# main_Sheet1.net
KiCad netlist of a schematic drawn in Altium Designer
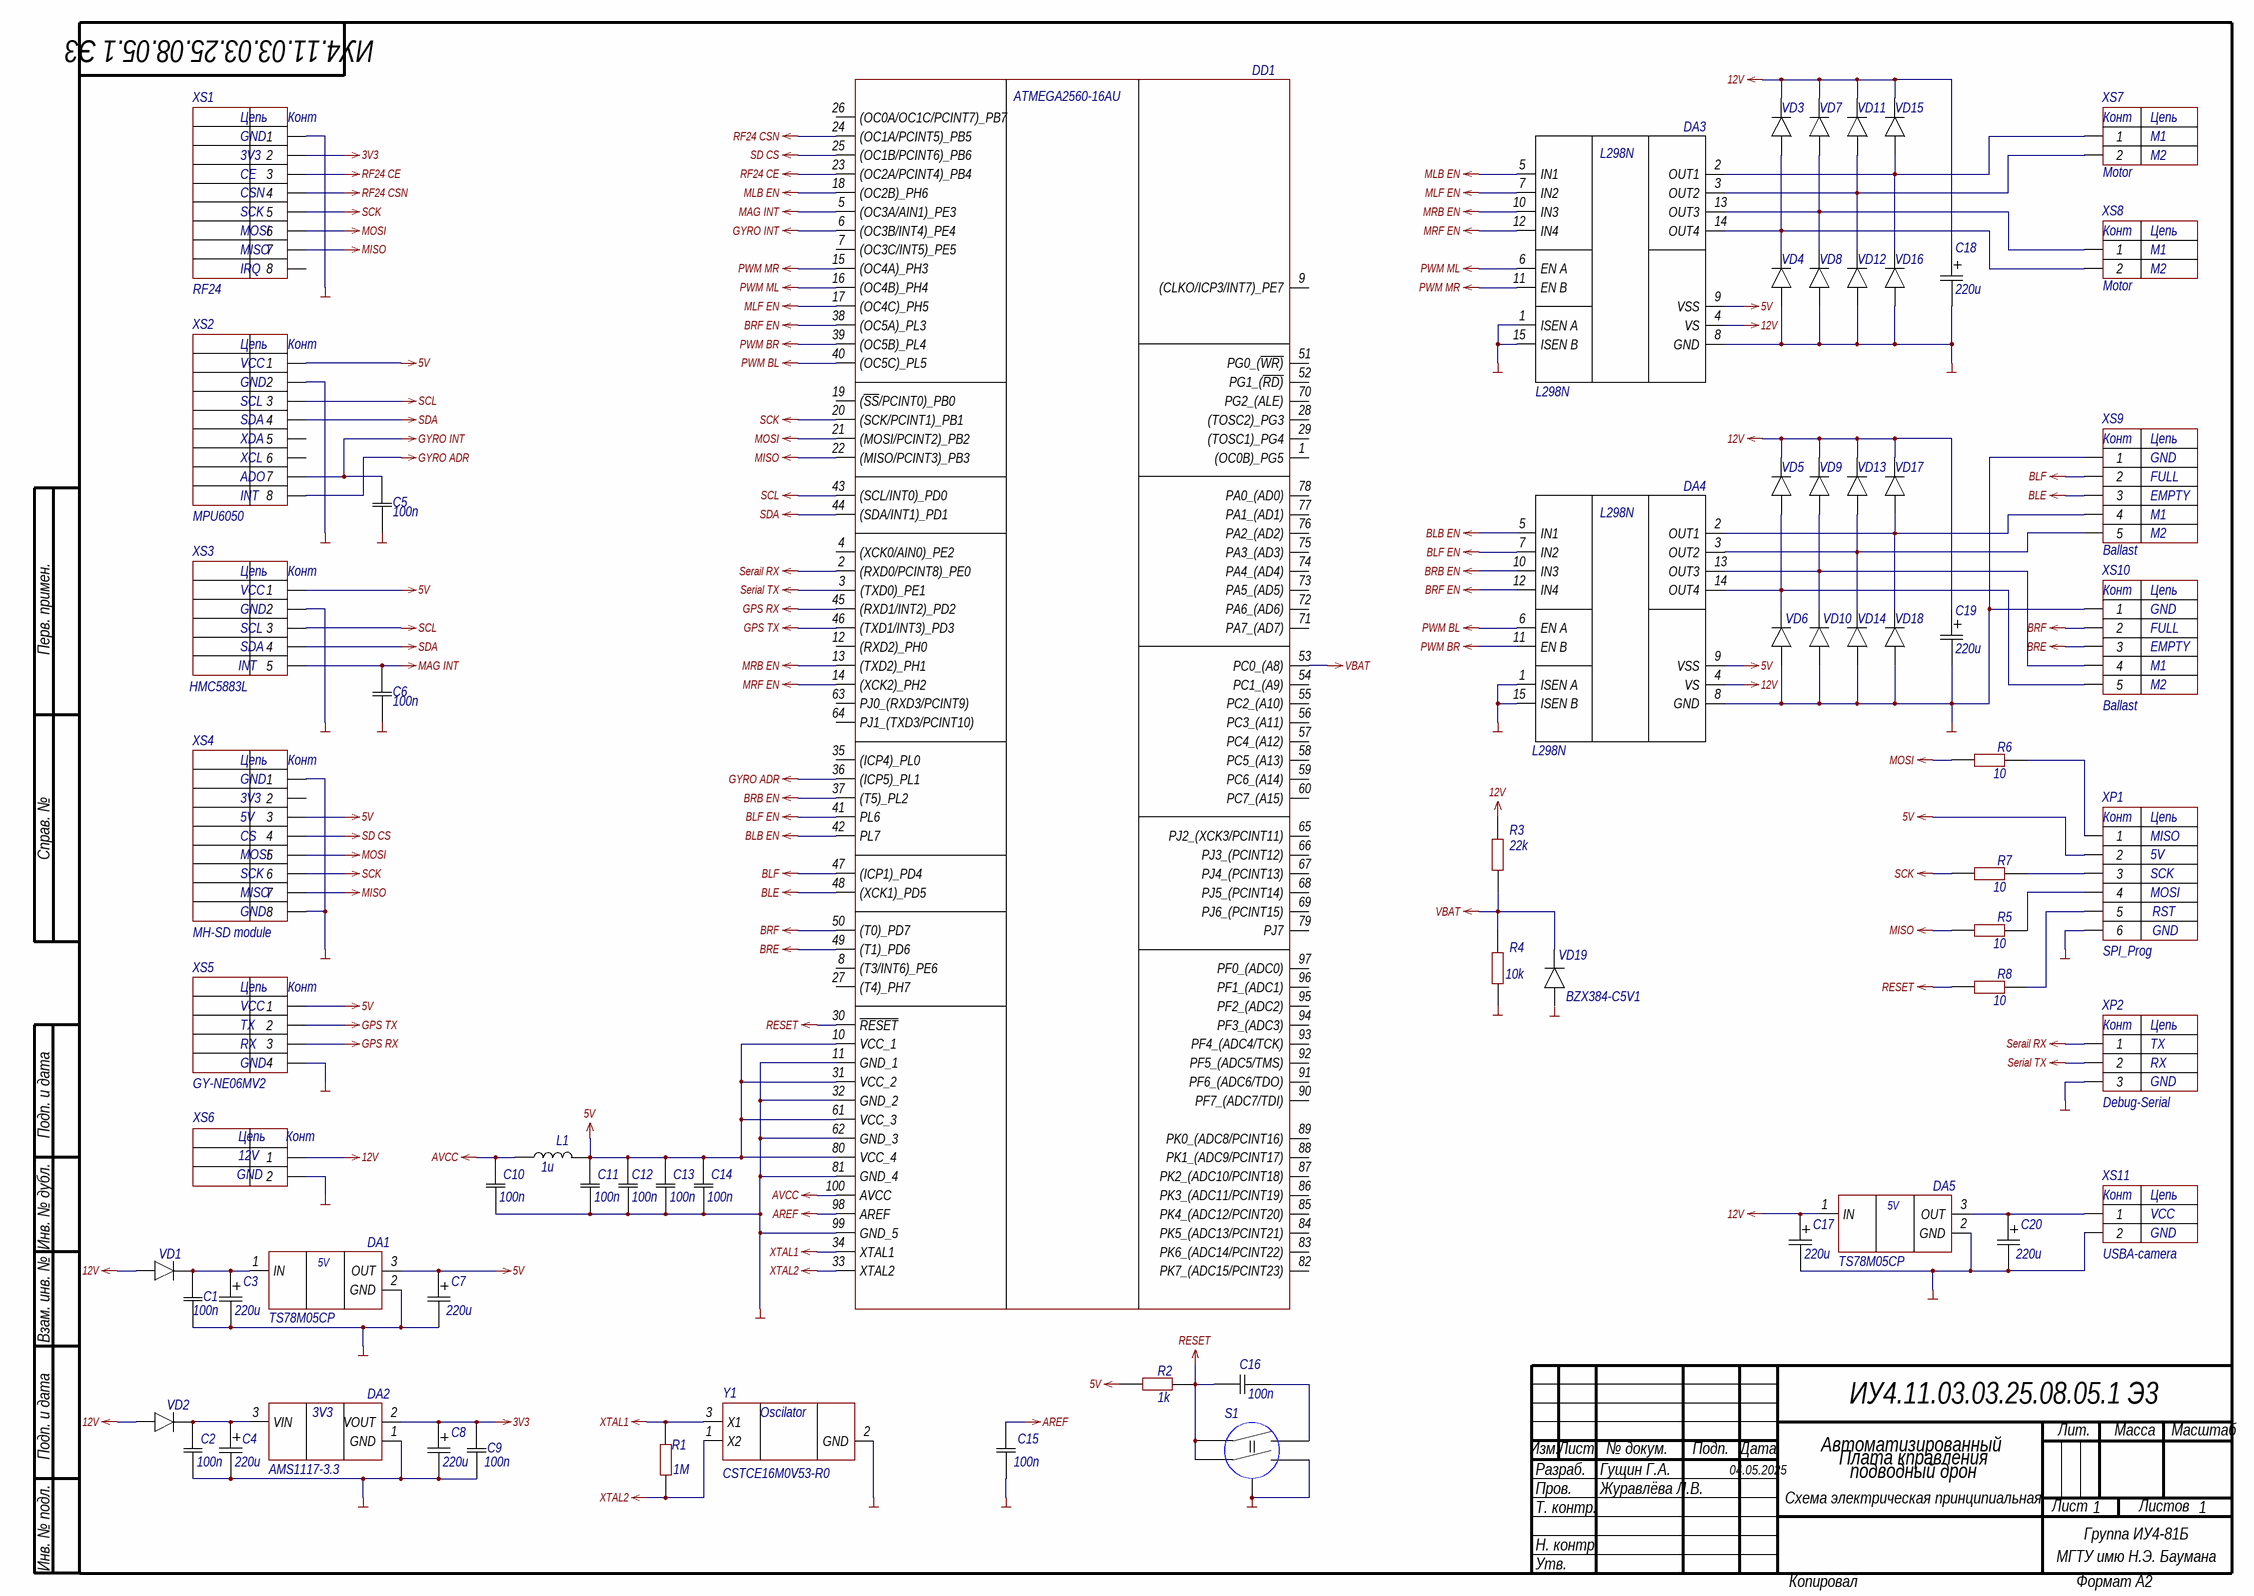
[diagram p0: main_Sheet1.SchDoc]

(export (version "E")
  (design (tool "Eeschema 10.0.6"))
  (components
    (comp (ref "C1")
      (value "100n")
      (footprint "main_PcbLib:CAPC3216X95N")
      (description "Capacitor")
      (fields
        (field (name "MANUFACTURER_PART_NUMBER") "GRM319R72A104KA01D")
        (field (name "MOUSER PART NUMBER") "81-GRM319R72A104KA1D")
      )
      (libsource (lib "main_SchLib") (part "GRM319R72A104KA01D"))
    )
    (comp (ref "C2")
      (value "100n")
      (footprint "main_PcbLib:CAPC3216X95N")
      (description "Capacitor")
      (fields
        (field (name "MANUFACTURER_PART_NUMBER") "GRM319R72A104KA01D")
        (field (name "MOUSER PART NUMBER") "81-GRM319R72A104KA1D")
      )
      (libsource (lib "main_SchLib") (part "GRM319R72A104KA01D"))
    )
    (comp (ref "C3")
      (value "220u")
      (footprint "main_PcbLib:CAPAE830X1050N")
      (description "Capacitor")
      (fields
        (field (name "MANUFACTURER_PART_NUMBER") "EMVY350ADA221MHA0G")
        (field (name "MOUSER PART NUMBER") "661-EMVY350ADA221MHA")
      )
      (libsource (lib "main_SchLib") (part "EMVY350ADA221MHA0G"))
    )
    (comp (ref "C4")
      (value "220u")
      (footprint "main_PcbLib:CAPAE830X1050N")
      (description "Capacitor")
      (fields
        (field (name "MANUFACTURER_PART_NUMBER") "EMVY350ADA221MHA0G")
        (field (name "MOUSER PART NUMBER") "661-EMVY350ADA221MHA")
      )
      (libsource (lib "main_SchLib") (part "EMVY350ADA221MHA0G"))
    )
    (comp (ref "C5")
      (value "100n")
      (footprint "main_PcbLib:CAPC3216X95N")
      (description "Capacitor")
      (fields
        (field (name "MANUFACTURER_PART_NUMBER") "GRM319R72A104KA01D")
        (field (name "MOUSER PART NUMBER") "81-GRM319R72A104KA1D")
      )
      (libsource (lib "main_SchLib") (part "GRM319R72A104KA01D"))
    )
    (comp (ref "C6")
      (value "100n")
      (footprint "main_PcbLib:CAPC3216X95N")
      (description "Capacitor")
      (fields
        (field (name "MANUFACTURER_PART_NUMBER") "GRM319R72A104KA01D")
        (field (name "MOUSER PART NUMBER") "81-GRM319R72A104KA1D")
      )
      (libsource (lib "main_SchLib") (part "GRM319R72A104KA01D"))
    )
    (comp (ref "C7")
      (value "220u")
      (footprint "main_PcbLib:CAPAE830X1050N")
      (description "Capacitor")
      (fields
        (field (name "MANUFACTURER_PART_NUMBER") "EMVY350ADA221MHA0G")
        (field (name "MOUSER PART NUMBER") "661-EMVY350ADA221MHA")
      )
      (libsource (lib "main_SchLib") (part "EMVY350ADA221MHA0G"))
    )
    (comp (ref "C8")
      (value "220u")
      (footprint "main_PcbLib:CAPAE830X1050N")
      (description "Capacitor")
      (fields
        (field (name "MANUFACTURER_PART_NUMBER") "EMVY350ADA221MHA0G")
        (field (name "MOUSER PART NUMBER") "661-EMVY350ADA221MHA")
      )
      (libsource (lib "main_SchLib") (part "EMVY350ADA221MHA0G"))
    )
    (comp (ref "C9")
      (value "100n")
      (footprint "main_PcbLib:CAPC3216X95N")
      (description "Capacitor")
      (fields
        (field (name "MANUFACTURER_PART_NUMBER") "GRM319R72A104KA01D")
        (field (name "MOUSER PART NUMBER") "81-GRM319R72A104KA1D")
      )
      (libsource (lib "main_SchLib") (part "GRM319R72A104KA01D"))
    )
    (comp (ref "C10")
      (value "100n")
      (footprint "main_PcbLib:CAPC3216X95N")
      (description "Capacitor")
      (fields
        (field (name "MANUFACTURER_PART_NUMBER") "GRM319R72A104KA01D")
        (field (name "MOUSER PART NUMBER") "81-GRM319R72A104KA1D")
      )
      (libsource (lib "main_SchLib") (part "GRM319R72A104KA01D"))
    )
    (comp (ref "C11")
      (value "100n")
      (footprint "main_PcbLib:CAPC3216X95N")
      (description "Capacitor")
      (fields
        (field (name "MANUFACTURER_PART_NUMBER") "GRM319R72A104KA01D")
        (field (name "MOUSER PART NUMBER") "81-GRM319R72A104KA1D")
      )
      (libsource (lib "main_SchLib") (part "GRM319R72A104KA01D"))
    )
    (comp (ref "C12")
      (value "100n")
      (footprint "main_PcbLib:CAPC3216X95N")
      (description "Capacitor")
      (fields
        (field (name "MANUFACTURER_PART_NUMBER") "GRM319R72A104KA01D")
        (field (name "MOUSER PART NUMBER") "81-GRM319R72A104KA1D")
      )
      (libsource (lib "main_SchLib") (part "GRM319R72A104KA01D"))
    )
    (comp (ref "C13")
      (value "100n")
      (footprint "main_PcbLib:CAPC3216X95N")
      (description "Capacitor")
      (fields
        (field (name "MANUFACTURER_PART_NUMBER") "GRM319R72A104KA01D")
        (field (name "MOUSER PART NUMBER") "81-GRM319R72A104KA1D")
      )
      (libsource (lib "main_SchLib") (part "GRM319R72A104KA01D"))
    )
    (comp (ref "C14")
      (value "100n")
      (footprint "main_PcbLib:CAPC3216X95N")
      (description "Capacitor")
      (fields
        (field (name "MANUFACTURER_PART_NUMBER") "GRM319R72A104KA01D")
        (field (name "MOUSER PART NUMBER") "81-GRM319R72A104KA1D")
      )
      (libsource (lib "main_SchLib") (part "GRM319R72A104KA01D"))
    )
    (comp (ref "C15")
      (value "100n")
      (footprint "main_PcbLib:CAPC3216X95N")
      (description "Capacitor")
      (fields
        (field (name "MANUFACTURER_PART_NUMBER") "GRM319R72A104KA01D")
        (field (name "MOUSER PART NUMBER") "81-GRM319R72A104KA1D")
      )
      (libsource (lib "main_SchLib") (part "GRM319R72A104KA01D"))
    )
    (comp (ref "C16")
      (value "100n")
      (footprint "main_PcbLib:CAPC3216X95N")
      (description "Capacitor")
      (fields
        (field (name "MANUFACTURER_PART_NUMBER") "GRM319R72A104KA01D")
        (field (name "MOUSER PART NUMBER") "81-GRM319R72A104KA1D")
      )
      (libsource (lib "main_SchLib") (part "GRM319R72A104KA01D"))
    )
    (comp (ref "C17")
      (value "220u")
      (footprint "main_PcbLib:CAPAE830X1050N")
      (description "Capacitor")
      (fields
        (field (name "MANUFACTURER_PART_NUMBER") "EMVY350ADA221MHA0G")
        (field (name "MOUSER PART NUMBER") "661-EMVY350ADA221MHA")
      )
      (libsource (lib "main_SchLib") (part "EMVY350ADA221MHA0G"))
    )
    (comp (ref "C18")
      (value "220u")
      (footprint "main_PcbLib:CAPAE830X1050N")
      (description "Capacitor")
      (fields
        (field (name "MANUFACTURER_PART_NUMBER") "EMVY350ADA221MHA0G")
        (field (name "MOUSER PART NUMBER") "661-EMVY350ADA221MHA")
      )
      (libsource (lib "main_SchLib") (part "EMVY350ADA221MHA0G"))
    )
    (comp (ref "C19")
      (value "220u")
      (footprint "main_PcbLib:CAPAE830X1050N")
      (description "Capacitor")
      (fields
        (field (name "MANUFACTURER_PART_NUMBER") "EMVY350ADA221MHA0G")
        (field (name "MOUSER PART NUMBER") "661-EMVY350ADA221MHA")
      )
      (libsource (lib "main_SchLib") (part "EMVY350ADA221MHA0G"))
    )
    (comp (ref "C20")
      (value "220u")
      (footprint "main_PcbLib:CAPAE830X1050N")
      (description "Capacitor")
      (fields
        (field (name "MANUFACTURER_PART_NUMBER") "EMVY350ADA221MHA0G")
        (field (name "MOUSER PART NUMBER") "661-EMVY350ADA221MHA")
      )
      (libsource (lib "main_SchLib") (part "EMVY350ADA221MHA0G"))
    )
    (comp (ref "DA1")
      (value "TS78M05CP")
      (footprint "main_PcbLib:TS78M05CP")
      (description "Integrated Circuit")
      (fields (field (name "MOUSER PART NUMBER") "821-TS78M05CP"))
      (libsource (lib "main_SchLib") (part "TS78M05CP"))
    )
    (comp (ref "DA2")
      (value "AMS1117-3.3")
      (footprint "main_PcbLib:SOT229P700X180-4N")
      (description "Integrated Circuit")
      (libsource (lib "main_SchLib") (part "AMS1117-3.3"))
    )
    (comp (ref "DA3")
      (value "L298N")
      (footprint "main_PcbLib:TO127P500X2020X2210-15P")
      (description "Integrated Circuit")
      (fields (field (name "MOUSER PART NUMBER") "511-L298"))
      (libsource (lib "main_SchLib") (part "L298N"))
    )
    (comp (ref "DA4")
      (value "L298N")
      (footprint "main_PcbLib:TO127P500X2020X2210-15P")
      (description "Integrated Circuit")
      (fields (field (name "MOUSER PART NUMBER") "511-L298"))
      (libsource (lib "main_SchLib") (part "L298N"))
    )
    (comp (ref "DA5")
      (value "TS78M05CP")
      (footprint "main_PcbLib:TS78M05CP")
      (description "Integrated Circuit")
      (fields (field (name "MOUSER PART NUMBER") "821-TS78M05CP"))
      (libsource (lib "main_SchLib") (part "TS78M05CP"))
    )
    (comp (ref "DD1")
      (value "ATMEGA2560-16AU")
      (footprint "main_PcbLib:QFP50P1600X1600X120-100N")
      (description "Integrated Circuit")
      (fields (field (name "MOUSER PART NUMBER") "556-ATMEGA2560-16AU"))
      (libsource (lib "main_SchLib") (part "ATMEGA2560-16AU"))
    )
    (comp (ref "L1")
      (value "1u")
      (footprint "main_PcbLib:INDPM3225X240N")
      (description "Inductor")
      (fields
        (field (name "MANUFACTURER_PART_NUMBER") "NLCV32T-1R0M-EF")
        (field (name "MOUSER PART NUMBER") "810-NLCV32T-1R0M-EF")
      )
      (libsource (lib "main_SchLib") (part "NLCV32T-1R0M-EF"))
    )
    (comp (ref "R1")
      (value "1M")
      (footprint "main_PcbLib:RESC3126X65N")
      (description "Resistor")
      (fields (field (name "MANUFACTURER_PART_NUMBER") "MP000277"))
      (libsource (lib "main_SchLib") (part "1M"))
    )
    (comp (ref "R2")
      (value "1k")
      (footprint "main_PcbLib:RESC3126X65N")
      (description "Resistor")
      (fields (field (name "MANUFACTURER_PART_NUMBER") "MP000277"))
      (libsource (lib "main_SchLib") (part "1k"))
    )
    (comp (ref "R3")
      (value "22k")
      (footprint "main_PcbLib:RESC3126X65N")
      (description "Resistor")
      (fields (field (name "MANUFACTURER_PART_NUMBER") "MP000277"))
      (libsource (lib "main_SchLib") (part "10k"))
    )
    (comp (ref "R4")
      (value "10k")
      (footprint "main_PcbLib:RESC3126X65N")
      (description "Resistor")
      (fields (field (name "MANUFACTURER_PART_NUMBER") "MP000277"))
      (libsource (lib "main_SchLib") (part "22k"))
    )
    (comp (ref "R5")
      (value "10")
      (footprint "main_PcbLib:RESC3126X65N")
      (description "Resistor")
      (fields (field (name "MANUFACTURER_PART_NUMBER") "MP000277"))
      (libsource (lib "main_SchLib") (part "10"))
    )
    (comp (ref "R6")
      (value "10")
      (footprint "main_PcbLib:RESC3126X65N")
      (description "Resistor")
      (fields (field (name "MANUFACTURER_PART_NUMBER") "MP000277"))
      (libsource (lib "main_SchLib") (part "10"))
    )
    (comp (ref "R7")
      (value "10")
      (footprint "main_PcbLib:RESC3126X65N")
      (description "Resistor")
      (fields (field (name "MANUFACTURER_PART_NUMBER") "MP000277"))
      (libsource (lib "main_SchLib") (part "10"))
    )
    (comp (ref "R8")
      (value "10")
      (footprint "main_PcbLib:RESC3126X65N")
      (description "Resistor")
      (fields (field (name "MANUFACTURER_PART_NUMBER") "MP000277"))
      (libsource (lib "main_SchLib") (part "10"))
    )
    (comp (ref "S1")
      (value "FSM1LPASTR")
      (footprint "main_PcbLib:FSM1LPASTR")
      (description "Switch")
      (fields (field (name "MOUSER PART NUMBER") "506-FSM1LPASTR"))
      (libsource (lib "main_SchLib") (part "FSM1LPASTR"))
    )
    (comp (ref "VD1")
      (value "~")
      (footprint "main_PcbLib:1N4007W")
      (description "Diode")
      (fields (field (name "MANUFACTURER_PART_NUMBER") "1N4007W"))
      (libsource (lib "main_SchLib") (part "1N4007W"))
    )
    (comp (ref "VD2")
      (value "1N4007W")
      (footprint "main_PcbLib:1N4007W")
      (description "Diode")
      (libsource (lib "main_SchLib") (part "1N4007W"))
    )
    (comp (ref "VD3")
      (value "1N4007W")
      (footprint "main_PcbLib:1N4007W")
      (description "Diode")
      (libsource (lib "main_SchLib") (part "1N4007W"))
    )
    (comp (ref "VD4")
      (value "1N4007W")
      (footprint "main_PcbLib:1N4007W")
      (description "Diode")
      (libsource (lib "main_SchLib") (part "1N4007W"))
    )
    (comp (ref "VD5")
      (value "1N4007W")
      (footprint "main_PcbLib:1N4007W")
      (description "Diode")
      (libsource (lib "main_SchLib") (part "1N4007W"))
    )
    (comp (ref "VD6")
      (value "1N4007W")
      (footprint "main_PcbLib:1N4007W")
      (description "Diode")
      (libsource (lib "main_SchLib") (part "1N4007W"))
    )
    (comp (ref "VD7")
      (value "1N4007W")
      (footprint "main_PcbLib:1N4007W")
      (description "Diode")
      (libsource (lib "main_SchLib") (part "1N4007W"))
    )
    (comp (ref "VD8")
      (value "1N4007W")
      (footprint "main_PcbLib:1N4007W")
      (description "Diode")
      (libsource (lib "main_SchLib") (part "1N4007W"))
    )
    (comp (ref "VD9")
      (value "1N4007W")
      (footprint "main_PcbLib:1N4007W")
      (description "Diode")
      (libsource (lib "main_SchLib") (part "1N4007W"))
    )
    (comp (ref "VD10")
      (value "1N4007W")
      (footprint "main_PcbLib:1N4007W")
      (description "Diode")
      (libsource (lib "main_SchLib") (part "1N4007W"))
    )
    (comp (ref "VD11")
      (value "1N4007W")
      (footprint "main_PcbLib:1N4007W")
      (description "Diode")
      (libsource (lib "main_SchLib") (part "1N4007W"))
    )
    (comp (ref "VD12")
      (value "1N4007W")
      (footprint "main_PcbLib:1N4007W")
      (description "Diode")
      (libsource (lib "main_SchLib") (part "1N4007W"))
    )
    (comp (ref "VD13")
      (value "1N4007W")
      (footprint "main_PcbLib:1N4007W")
      (description "Diode")
      (libsource (lib "main_SchLib") (part "1N4007W"))
    )
    (comp (ref "VD14")
      (value "1N4007W")
      (footprint "main_PcbLib:1N4007W")
      (description "Diode")
      (libsource (lib "main_SchLib") (part "1N4007W"))
    )
    (comp (ref "VD15")
      (value "1N4007W")
      (footprint "main_PcbLib:1N4007W")
      (description "Diode")
      (libsource (lib "main_SchLib") (part "1N4007W"))
    )
    (comp (ref "VD16")
      (value "1N4007W")
      (footprint "main_PcbLib:1N4007W")
      (description "Diode")
      (libsource (lib "main_SchLib") (part "1N4007W"))
    )
    (comp (ref "VD17")
      (value "1N4007W")
      (footprint "main_PcbLib:1N4007W")
      (description "Diode")
      (libsource (lib "main_SchLib") (part "1N4007W"))
    )
    (comp (ref "VD18")
      (value "1N4007W")
      (footprint "main_PcbLib:1N4007W")
      (description "Diode")
      (libsource (lib "main_SchLib") (part "1N4007W"))
    )
    (comp (ref "VD19")
      (value "BZX384-C5V1")
      (footprint "main_PcbLib:SOD2512X110N")
      (description "Diode")
      (libsource (lib "main_SchLib") (part "BZX384-C5V1"))
    )
    (comp (ref "XP1")
      (value "SPI_Prog")
      (footprint "PLS_2x3")
      (description "Connector")
      (libsource (lib "main_SchLib") (part "SPI_Prog"))
    )
    (comp (ref "XP2")
      (value "Debug-Serial")
      (footprint "PLS_1x3")
      (description "Connector")
      (libsource (lib "main_SchLib") (part "Debug-Serial"))
    )
    (comp (ref "XS1")
      (value "RF24")
      (footprint "nRF24")
      (description "Connector")
      (libsource (lib "main_SchLib") (part "nRF24"))
    )
    (comp (ref "XS2")
      (value "MPU6050")
      (footprint "MPU6050")
      (description "Connector")
      (libsource (lib "main_SchLib") (part "MPU6050"))
    )
    (comp (ref "XS3")
      (value "HMC5883L")
      (footprint "HMC5883L")
      (description "Connector")
      (libsource (lib "main_SchLib") (part "HMC5883L"))
    )
    (comp (ref "XS4")
      (value "MH-SD module")
      (footprint "SD-module")
      (description "Connector")
      (libsource (lib "main_SchLib") (part "MH-SD module"))
    )
    (comp (ref "XS5")
      (value "GY-NE06MV2")
      (footprint "GY-GPS")
      (description "Connector")
      (libsource (lib "main_SchLib") (part "GY-NE06MV2"))
    )
    (comp (ref "XS6")
      (value "XT60PW-M")
      (footprint "main_PcbLib:XT60PWM")
      (description "Connector")
      (libsource (lib "main_SchLib") (part "XT60PW-M"))
    )
    (comp (ref "XS7")
      (value "Motor")
      (footprint "S2B-XH-A-1")
      (description "Connector")
      (libsource (lib "main_SchLib") (part "Motor"))
    )
    (comp (ref "XS8")
      (value "Motor")
      (footprint "S2B-XH-A-1")
      (description "Connector")
      (libsource (lib "main_SchLib") (part "Motor"))
    )
    (comp (ref "XS9")
      (value "Ballast")
      (footprint "S5B-XH-A-1")
      (description "Connector")
      (libsource (lib "main_SchLib") (part "Ballast"))
    )
    (comp (ref "XS10")
      (value "Ballast")
      (footprint "S5B-XH-A-1")
      (description "Connector")
      (libsource (lib "main_SchLib") (part "Ballast"))
    )
    (comp (ref "XS11")
      (value "USBA-camera")
      (footprint "TYPE-C-SMD")
      (description "Connector")
      (libsource (lib "main_SchLib") (part "USBA-camera"))
    )
    (comp (ref "Y1")
      (value "CSTCE16M0V53-R0")
      (footprint "main_PcbLib:CSTCE16M0V53R0")
      (description "Oscillator")
      (fields (field (name "MOUSER PART NUMBER") "81-CSTCE16M0V53-R0"))
      (libsource (lib "main_SchLib") (part "CSTCE16M0V53-R0"))
    )
  )
  (nets
    (net (code "1") (name "3V3") (class "Default")
      (node (ref "C8") (pin "1") (pinfunction "+_1") (pintype "passive"))
      (node (ref "C9") (pin "1") (pinfunction "1_1") (pintype "passive"))
      (node (ref "DA2") (pin "2") (pinfunction "VOUT_2") (pintype "passive"))
      (node (ref "XS1") (pin "2") (pinfunction "2_2") (pintype "passive"))
    )
    (net (code "2") (name "5V") (class "Default")
      (node (ref "C11") (pin "1") (pinfunction "1_1") (pintype "passive"))
      (node (ref "C12") (pin "1") (pinfunction "1_1") (pintype "passive"))
      (node (ref "C13") (pin "1") (pinfunction "1_1") (pintype "passive"))
      (node (ref "C14") (pin "1") (pinfunction "1_1") (pintype "passive"))
      (node (ref "C7") (pin "1") (pinfunction "+_1") (pintype "passive"))
      (node (ref "DA1") (pin "3") (pinfunction "OUT_3") (pintype "passive"))
      (node (ref "DA3") (pin "9") (pinfunction "VSS_9") (pintype "power_in"))
      (node (ref "DA4") (pin "9") (pinfunction "VSS_9") (pintype "power_in"))
      (node (ref "DD1") (pin "10") (pinfunction "VCC_1_10") (pintype "passive"))
      (node (ref "DD1") (pin "31") (pinfunction "VCC_2_31") (pintype "passive"))
      (node (ref "DD1") (pin "61") (pinfunction "VCC_3_61") (pintype "passive"))
      (node (ref "DD1") (pin "80") (pinfunction "VCC_4_80") (pintype "passive"))
      (node (ref "L1") (pin "2") (pinfunction "2_2") (pintype "passive"))
      (node (ref "R2") (pin "1") (pinfunction "1_1") (pintype "passive"))
      (node (ref "XP1") (pin "2") (pinfunction "2_2") (pintype "passive"))
      (node (ref "XS2") (pin "1") (pinfunction "1_1") (pintype "passive"))
      (node (ref "XS3") (pin "1") (pinfunction "1_1") (pintype "passive"))
      (node (ref "XS4") (pin "3") (pinfunction "3_3") (pintype "passive"))
      (node (ref "XS5") (pin "1") (pinfunction "1_1") (pintype "passive"))
    )
    (net (code "3") (name "12V") (class "Default")
      (node (ref "C17") (pin "1") (pinfunction "+_1") (pintype "passive"))
      (node (ref "C18") (pin "1") (pinfunction "+_1") (pintype "passive"))
      (node (ref "C19") (pin "1") (pinfunction "+_1") (pintype "passive"))
      (node (ref "DA3") (pin "4") (pinfunction "VS_4") (pintype "power_in"))
      (node (ref "DA4") (pin "4") (pinfunction "VS_4") (pintype "power_in"))
      (node (ref "DA5") (pin "1") (pinfunction "IN_1") (pintype "passive"))
      (node (ref "R3") (pin "2") (pinfunction "2_2") (pintype "passive"))
      (node (ref "VD1") (pin "2") (pinfunction "A_2") (pintype "passive"))
      (node (ref "VD11") (pin "1") (pinfunction "K_1") (pintype "passive"))
      (node (ref "VD13") (pin "1") (pinfunction "K_1") (pintype "passive"))
      (node (ref "VD15") (pin "1") (pinfunction "K_1") (pintype "passive"))
      (node (ref "VD17") (pin "1") (pinfunction "K_1") (pintype "passive"))
      (node (ref "VD2") (pin "2") (pinfunction "A_2") (pintype "passive"))
      (node (ref "VD3") (pin "1") (pinfunction "K_1") (pintype "passive"))
      (node (ref "VD5") (pin "1") (pinfunction "K_1") (pintype "passive"))
      (node (ref "VD7") (pin "1") (pinfunction "K_1") (pintype "passive"))
      (node (ref "VD9") (pin "1") (pinfunction "K_1") (pintype "passive"))
      (node (ref "XS6") (pin "1") (pinfunction "1_1") (pintype "passive"))
    )
    (net (code "4") (name "AREF") (class "Default")
      (node (ref "C15") (pin "1") (pinfunction "1_1") (pintype "passive"))
      (node (ref "DD1") (pin "98") (pinfunction "AREF_98") (pintype "passive"))
    )
    (net (code "5") (name "AVCC") (class "Default")
      (node (ref "C10") (pin "1") (pinfunction "1_1") (pintype "passive"))
      (node (ref "DD1") (pin "100") (pinfunction "AVCC_100") (pintype "passive"))
      (node (ref "L1") (pin "1") (pinfunction "1_1") (pintype "passive"))
    )
    (net (code "6") (name "BLB EN") (class "Default")
      (node (ref "DA4") (pin "5") (pinfunction "IN1_5") (pintype "power_in"))
      (node (ref "DD1") (pin "42") (pinfunction "PL7_42") (pintype "passive"))
    )
    (net (code "7") (name "BLE") (class "Default")
      (node (ref "DD1") (pin "48") (pinfunction "(XCK1)_PD5_48") (pintype "passive"))
      (node (ref "XS9") (pin "3") (pinfunction "3_3") (pintype "passive"))
    )
    (net (code "8") (name "BLF") (class "Default")
      (node (ref "DD1") (pin "47") (pinfunction "(ICP1)_PD4_47") (pintype "passive"))
      (node (ref "XS9") (pin "2") (pinfunction "2_2") (pintype "passive"))
    )
    (net (code "9") (name "BLF EN") (class "Default")
      (node (ref "DA4") (pin "7") (pinfunction "IN2_7") (pintype "power_in"))
      (node (ref "DD1") (pin "41") (pinfunction "PL6_41") (pintype "passive"))
    )
    (net (code "10") (name "BRB EN") (class "Default")
      (node (ref "DA4") (pin "10") (pinfunction "IN3_10") (pintype "power_in"))
      (node (ref "DD1") (pin "37") (pinfunction "(T5)_PL2_37") (pintype "passive"))
    )
    (net (code "11") (name "BRE") (class "Default")
      (node (ref "DD1") (pin "49") (pinfunction "(T1)_PD6_49") (pintype "passive"))
      (node (ref "XS10") (pin "3") (pinfunction "3_3") (pintype "passive"))
    )
    (net (code "12") (name "BRF") (class "Default")
      (node (ref "DD1") (pin "50") (pinfunction "(T0)_PD7_50") (pintype "passive"))
      (node (ref "XS10") (pin "2") (pinfunction "2_2") (pintype "passive"))
    )
    (net (code "13") (name "BRF EN") (class "Default")
      (node (ref "DA4") (pin "12") (pinfunction "IN4_12") (pintype "power_in"))
      (node (ref "DD1") (pin "38") (pinfunction "(OC5A)_PL3_38") (pintype "passive"))
    )
    (net (code "14") (name "GND") (class "Default")
      (node (ref "C1") (pin "2") (pinfunction "2_2") (pintype "passive"))
      (node (ref "C10") (pin "2") (pinfunction "2_2") (pintype "passive"))
      (node (ref "C11") (pin "2") (pinfunction "2_2") (pintype "passive"))
      (node (ref "C12") (pin "2") (pinfunction "2_2") (pintype "passive"))
      (node (ref "C13") (pin "2") (pinfunction "2_2") (pintype "passive"))
      (node (ref "C14") (pin "2") (pinfunction "2_2") (pintype "passive"))
      (node (ref "C15") (pin "2") (pinfunction "2_2") (pintype "passive"))
      (node (ref "C17") (pin "2") (pinfunction "-_2") (pintype "passive"))
      (node (ref "C18") (pin "2") (pinfunction "-_2") (pintype "passive"))
      (node (ref "C19") (pin "2") (pinfunction "-_2") (pintype "passive"))
      (node (ref "C2") (pin "2") (pinfunction "2_2") (pintype "passive"))
      (node (ref "C20") (pin "2") (pinfunction "-_2") (pintype "passive"))
      (node (ref "C3") (pin "2") (pinfunction "-_2") (pintype "passive"))
      (node (ref "C4") (pin "2") (pinfunction "-_2") (pintype "passive"))
      (node (ref "C5") (pin "2") (pinfunction "2_2") (pintype "passive"))
      (node (ref "C6") (pin "2") (pinfunction "2_2") (pintype "passive"))
      (node (ref "C7") (pin "2") (pinfunction "-_2") (pintype "passive"))
      (node (ref "C8") (pin "2") (pinfunction "-_2") (pintype "passive"))
      (node (ref "C9") (pin "2") (pinfunction "2_2") (pintype "passive"))
      (node (ref "DA1") (pin "2") (pinfunction "GND_2") (pintype "passive"))
      (node (ref "DA2") (pin "1") (pinfunction "GND_1") (pintype "passive"))
      (node (ref "DA3") (pin "1") (pinfunction "ISEN_A_1") (pintype "power_in"))
      (node (ref "DA3") (pin "15") (pinfunction "ISEN_B_15") (pintype "power_in"))
      (node (ref "DA3") (pin "8") (pinfunction "GND_8") (pintype "power_in"))
      (node (ref "DA4") (pin "1") (pinfunction "ISEN_A_1") (pintype "power_in"))
      (node (ref "DA4") (pin "15") (pinfunction "ISEN_B_15") (pintype "power_in"))
      (node (ref "DA4") (pin "8") (pinfunction "GND_8") (pintype "power_in"))
      (node (ref "DA5") (pin "2") (pinfunction "GND_2") (pintype "passive"))
      (node (ref "DD1") (pin "11") (pinfunction "GND_1_11") (pintype "passive"))
      (node (ref "DD1") (pin "32") (pinfunction "GND_2_32") (pintype "passive"))
      (node (ref "DD1") (pin "62") (pinfunction "GND_3_62") (pintype "passive"))
      (node (ref "DD1") (pin "81") (pinfunction "GND_4_81") (pintype "passive"))
      (node (ref "DD1") (pin "99") (pinfunction "GND_5_99") (pintype "passive"))
      (node (ref "R4") (pin "1") (pinfunction "1_1") (pintype "passive"))
      (node (ref "S1") (pin "4") (pinfunction "NO_2_4") (pintype "passive"))
      (node (ref "S1") (pin "5") (pinfunction "GND_5") (pintype "passive"))
      (node (ref "VD10") (pin "2") (pinfunction "A_2") (pintype "passive"))
      (node (ref "VD12") (pin "2") (pinfunction "A_2") (pintype "passive"))
      (node (ref "VD14") (pin "2") (pinfunction "A_2") (pintype "passive"))
      (node (ref "VD16") (pin "2") (pinfunction "A_2") (pintype "passive"))
      (node (ref "VD18") (pin "2") (pinfunction "A_2") (pintype "passive"))
      (node (ref "VD4") (pin "2") (pinfunction "A_2") (pintype "passive"))
      (node (ref "VD6") (pin "2") (pinfunction "A_2") (pintype "passive"))
      (node (ref "VD8") (pin "2") (pinfunction "A_2") (pintype "passive"))
      (node (ref "XP1") (pin "6") (pinfunction "6_6") (pintype "passive"))
      (node (ref "XP2") (pin "3") (pinfunction "3_3") (pintype "passive"))
      (node (ref "XS1") (pin "1") (pinfunction "1_1") (pintype "passive"))
      (node (ref "XS10") (pin "1") (pinfunction "1_1") (pintype "passive"))
      (node (ref "XS11") (pin "4") (pinfunction "2_4") (pintype "passive"))
      (node (ref "XS2") (pin "2") (pinfunction "2_2") (pintype "passive"))
      (node (ref "XS3") (pin "2") (pinfunction "2_2") (pintype "passive"))
      (node (ref "XS4") (pin "1") (pinfunction "1_1") (pintype "passive"))
      (node (ref "XS4") (pin "8") (pinfunction "8_8") (pintype "passive"))
      (node (ref "XS5") (pin "4") (pinfunction "4_4") (pintype "passive"))
      (node (ref "XS6") (pin "2") (pinfunction "2_2") (pintype "passive"))
      (node (ref "XS9") (pin "1") (pinfunction "1_1") (pintype "passive"))
      (node (ref "Y1") (pin "2") (pinfunction "GND_2") (pintype "passive"))
    )
    (net (code "15") (name "GPS RX") (class "Default")
      (node (ref "DD1") (pin "45") (pinfunction "(RXD1/INT2)_PD2_45") (pintype "passive"))
      (node (ref "XS5") (pin "3") (pinfunction "3_3") (pintype "passive"))
    )
    (net (code "16") (name "GPS TX") (class "Default")
      (node (ref "DD1") (pin "46") (pinfunction "(TXD1/INT3)_PD3_46") (pintype "passive"))
      (node (ref "XS5") (pin "2") (pinfunction "2_2") (pintype "passive"))
    )
    (net (code "17") (name "GYRO ADR") (class "Default")
      (node (ref "DD1") (pin "36") (pinfunction "(ICP5)_PL1_36") (pintype "passive"))
      (node (ref "XS2") (pin "8") (pinfunction "8_8") (pintype "passive"))
    )
    (net (code "18") (name "GYRO INT") (class "Default")
      (node (ref "C5") (pin "1") (pinfunction "1_1") (pintype "passive"))
      (node (ref "DD1") (pin "6") (pinfunction "(OC3B/INT4)_PE4_6") (pintype "passive"))
      (node (ref "XS2") (pin "7") (pinfunction "7_7") (pintype "passive"))
    )
    (net (code "19") (name "MAG INT") (class "Default")
      (node (ref "C6") (pin "1") (pinfunction "1_1") (pintype "passive"))
      (node (ref "DD1") (pin "5") (pinfunction "(OC3A/AIN1)_PE3_5") (pintype "passive"))
      (node (ref "XS3") (pin "5") (pinfunction "5_5") (pintype "passive"))
    )
    (net (code "20") (name "MISO") (class "Default")
      (node (ref "DD1") (pin "22") (pinfunction "(MISO/PCINT3)_PB3_22") (pintype "passive"))
      (node (ref "R5") (pin "1") (pinfunction "1_1") (pintype "passive"))
      (node (ref "XS1") (pin "7") (pinfunction "7_7") (pintype "passive"))
      (node (ref "XS4") (pin "7") (pinfunction "7_7") (pintype "passive"))
    )
    (net (code "21") (name "MLB EN") (class "Default")
      (node (ref "DA3") (pin "5") (pinfunction "IN1_5") (pintype "power_in"))
      (node (ref "DD1") (pin "18") (pinfunction "(OC2B)_PH6_18") (pintype "passive"))
    )
    (net (code "22") (name "MLF EN") (class "Default")
      (node (ref "DA3") (pin "7") (pinfunction "IN2_7") (pintype "power_in"))
      (node (ref "DD1") (pin "17") (pinfunction "(OC4C)_PH5_17") (pintype "passive"))
    )
    (net (code "23") (name "MOSI") (class "Default")
      (node (ref "DD1") (pin "21") (pinfunction "(MOSI/PCINT2)_PB2_21") (pintype "passive"))
      (node (ref "R6") (pin "1") (pinfunction "1_1") (pintype "passive"))
      (node (ref "XS1") (pin "6") (pinfunction "6_6") (pintype "passive"))
      (node (ref "XS4") (pin "5") (pinfunction "5_5") (pintype "passive"))
    )
    (net (code "24") (name "MRB EN") (class "Default")
      (node (ref "DA3") (pin "10") (pinfunction "IN3_10") (pintype "power_in"))
      (node (ref "DD1") (pin "13") (pinfunction "(TXD2)_PH1_13") (pintype "passive"))
    )
    (net (code "25") (name "MRF EN") (class "Default")
      (node (ref "DA3") (pin "12") (pinfunction "IN4_12") (pintype "power_in"))
      (node (ref "DD1") (pin "14") (pinfunction "(XCK2)_PH2_14") (pintype "passive"))
    )
    (net (code "26") (name "Net-(C3-+)") (class "Default")
      (node (ref "C1") (pin "1") (pinfunction "1_1") (pintype "passive"))
      (node (ref "C3") (pin "1") (pinfunction "+_1") (pintype "passive"))
      (node (ref "DA1") (pin "1") (pinfunction "IN_1") (pintype "passive"))
      (node (ref "VD1") (pin "1") (pinfunction "K_1") (pintype "passive"))
    )
    (net (code "27") (name "Net-(C4-+)") (class "Default")
      (node (ref "C2") (pin "1") (pinfunction "1_1") (pintype "passive"))
      (node (ref "C4") (pin "1") (pinfunction "+_1") (pintype "passive"))
      (node (ref "DA2") (pin "3") (pinfunction "VIN_3") (pintype "passive"))
      (node (ref "VD2") (pin "1") (pinfunction "K_1") (pintype "passive"))
    )
    (net (code "28") (name "Net-(C20-+)") (class "Default")
      (node (ref "C20") (pin "1") (pinfunction "+_1") (pintype "passive"))
      (node (ref "DA5") (pin "3") (pinfunction "OUT_3") (pintype "passive"))
      (node (ref "XS11") (pin "1") (pinfunction "1_1") (pintype "passive"))
    )
    (net (code "29") (name "Net-(DA3-OUT1)") (class "Default")
      (node (ref "DA3") (pin "2") (pinfunction "OUT1_2") (pintype "power_in"))
      (node (ref "VD15") (pin "2") (pinfunction "A_2") (pintype "passive"))
      (node (ref "VD16") (pin "1") (pinfunction "K_1") (pintype "passive"))
      (node (ref "XS7") (pin "1") (pinfunction "1_1") (pintype "passive"))
    )
    (net (code "30") (name "Net-(DA3-OUT2)") (class "Default")
      (node (ref "DA3") (pin "3") (pinfunction "OUT2_3") (pintype "power_in"))
      (node (ref "VD11") (pin "2") (pinfunction "A_2") (pintype "passive"))
      (node (ref "VD12") (pin "1") (pinfunction "K_1") (pintype "passive"))
      (node (ref "XS7") (pin "2") (pinfunction "2_2") (pintype "passive"))
    )
    (net (code "31") (name "Net-(DA3-OUT3)") (class "Default")
      (node (ref "DA3") (pin "13") (pinfunction "OUT3_13") (pintype "power_in"))
      (node (ref "VD7") (pin "2") (pinfunction "A_2") (pintype "passive"))
      (node (ref "VD8") (pin "1") (pinfunction "K_1") (pintype "passive"))
      (node (ref "XS8") (pin "1") (pinfunction "1_1") (pintype "passive"))
    )
    (net (code "32") (name "Net-(DA3-OUT4)") (class "Default")
      (node (ref "DA3") (pin "14") (pinfunction "OUT4_14") (pintype "power_in"))
      (node (ref "VD3") (pin "2") (pinfunction "A_2") (pintype "passive"))
      (node (ref "VD4") (pin "1") (pinfunction "K_1") (pintype "passive"))
      (node (ref "XS8") (pin "2") (pinfunction "2_2") (pintype "passive"))
    )
    (net (code "33") (name "Net-(DA4-OUT1)") (class "Default")
      (node (ref "DA4") (pin "2") (pinfunction "OUT1_2") (pintype "power_in"))
      (node (ref "VD17") (pin "2") (pinfunction "A_2") (pintype "passive"))
      (node (ref "VD18") (pin "1") (pinfunction "K_1") (pintype "passive"))
      (node (ref "XS9") (pin "4") (pinfunction "4_4") (pintype "passive"))
    )
    (net (code "34") (name "Net-(DA4-OUT2)") (class "Default")
      (node (ref "DA4") (pin "3") (pinfunction "OUT2_3") (pintype "power_in"))
      (node (ref "VD13") (pin "2") (pinfunction "A_2") (pintype "passive"))
      (node (ref "VD14") (pin "1") (pinfunction "K_1") (pintype "passive"))
      (node (ref "XS9") (pin "5") (pinfunction "5_5") (pintype "passive"))
    )
    (net (code "35") (name "Net-(DA4-OUT3)") (class "Default")
      (node (ref "DA4") (pin "13") (pinfunction "OUT3_13") (pintype "power_in"))
      (node (ref "VD10") (pin "1") (pinfunction "K_1") (pintype "passive"))
      (node (ref "VD9") (pin "2") (pinfunction "A_2") (pintype "passive"))
      (node (ref "XS10") (pin "4") (pinfunction "4_4") (pintype "passive"))
    )
    (net (code "36") (name "Net-(DA4-OUT4)") (class "Default")
      (node (ref "DA4") (pin "14") (pinfunction "OUT4_14") (pintype "power_in"))
      (node (ref "VD5") (pin "2") (pinfunction "A_2") (pintype "passive"))
      (node (ref "VD6") (pin "1") (pinfunction "K_1") (pintype "passive"))
      (node (ref "XS10") (pin "5") (pinfunction "5_5") (pintype "passive"))
    )
    (net (code "37") (name "Net-(R5-Pad2)") (class "Default")
      (node (ref "R5") (pin "2") (pinfunction "2_2") (pintype "passive"))
      (node (ref "XP1") (pin "4") (pinfunction "4_4") (pintype "passive"))
    )
    (net (code "38") (name "Net-(R6-Pad2)") (class "Default")
      (node (ref "R6") (pin "2") (pinfunction "2_2") (pintype "passive"))
      (node (ref "XP1") (pin "1") (pinfunction "1_1") (pintype "passive"))
    )
    (net (code "39") (name "Net-(R7-Pad2)") (class "Default")
      (node (ref "R7") (pin "2") (pinfunction "2_2") (pintype "passive"))
      (node (ref "XP1") (pin "3") (pinfunction "3_3") (pintype "passive"))
    )
    (net (code "40") (name "Net-(R8-Pad2)") (class "Default")
      (node (ref "R8") (pin "2") (pinfunction "2_2") (pintype "passive"))
      (node (ref "XP1") (pin "5") (pinfunction "5_5") (pintype "passive"))
    )
    (net (code "41") (name "Net-(S1-NO_1)") (class "Default")
      (node (ref "C16") (pin "2") (pinfunction "2_2") (pintype "passive"))
      (node (ref "S1") (pin "3") (pinfunction "NO_1_3") (pintype "passive"))
    )
    (net (code "42") (name "PWM BL") (class "Default")
      (node (ref "DA4") (pin "6") (pinfunction "EN_A_6") (pintype "power_in"))
      (node (ref "DD1") (pin "40") (pinfunction "(OC5C)_PL5_40") (pintype "passive"))
    )
    (net (code "43") (name "PWM BR") (class "Default")
      (node (ref "DA4") (pin "11") (pinfunction "EN_B_11") (pintype "power_in"))
      (node (ref "DD1") (pin "39") (pinfunction "(OC5B)_PL4_39") (pintype "passive"))
    )
    (net (code "44") (name "PWM ML") (class "Default")
      (node (ref "DA3") (pin "6") (pinfunction "EN_A_6") (pintype "power_in"))
      (node (ref "DD1") (pin "16") (pinfunction "(OC4B)_PH4_16") (pintype "passive"))
    )
    (net (code "45") (name "PWM MR") (class "Default")
      (node (ref "DA3") (pin "11") (pinfunction "EN_B_11") (pintype "power_in"))
      (node (ref "DD1") (pin "15") (pinfunction "(OC4A)_PH3_15") (pintype "passive"))
    )
    (net (code "46") (name "RESET") (class "Default")
      (node (ref "C16") (pin "1") (pinfunction "1_1") (pintype "passive"))
      (node (ref "DD1") (pin "30") (pinfunction "~{RESET}_30") (pintype "passive"))
      (node (ref "R2") (pin "2") (pinfunction "2_2") (pintype "passive"))
      (node (ref "R8") (pin "1") (pinfunction "1_1") (pintype "passive"))
      (node (ref "S1") (pin "1") (pinfunction "COM_1_1") (pintype "passive"))
      (node (ref "S1") (pin "2") (pinfunction "COM_2_2") (pintype "passive"))
    )
    (net (code "47") (name "RF24 CE") (class "Default")
      (node (ref "DD1") (pin "23") (pinfunction "(OC2A/PCINT4)_PB4_23") (pintype "passive"))
      (node (ref "XS1") (pin "3") (pinfunction "3_3") (pintype "passive"))
    )
    (net (code "48") (name "RF24 CSN") (class "Default")
      (node (ref "DD1") (pin "24") (pinfunction "(OC1A/PCINT5)_PB5_24") (pintype "passive"))
      (node (ref "XS1") (pin "4") (pinfunction "4_4") (pintype "passive"))
    )
    (net (code "49") (name "SCK") (class "Default")
      (node (ref "DD1") (pin "20") (pinfunction "(SCK/PCINT1)_PB1_20") (pintype "passive"))
      (node (ref "R7") (pin "1") (pinfunction "1_1") (pintype "passive"))
      (node (ref "XS1") (pin "5") (pinfunction "5_5") (pintype "passive"))
      (node (ref "XS4") (pin "6") (pinfunction "6_6") (pintype "passive"))
    )
    (net (code "50") (name "SCL") (class "Default")
      (node (ref "DD1") (pin "43") (pinfunction "(SCL/INT0)_PD0_43") (pintype "passive"))
      (node (ref "XS2") (pin "3") (pinfunction "3_3") (pintype "passive"))
      (node (ref "XS3") (pin "3") (pinfunction "3_3") (pintype "passive"))
    )
    (net (code "51") (name "SD CS") (class "Default")
      (node (ref "DD1") (pin "25") (pinfunction "(OC1B/PCINT6)_PB6_25") (pintype "passive"))
      (node (ref "XS4") (pin "4") (pinfunction "4_4") (pintype "passive"))
    )
    (net (code "52") (name "SDA") (class "Default")
      (node (ref "DD1") (pin "44") (pinfunction "(SDA/INT1)_PD1_44") (pintype "passive"))
      (node (ref "XS2") (pin "4") (pinfunction "4_4") (pintype "passive"))
      (node (ref "XS3") (pin "4") (pinfunction "4_4") (pintype "passive"))
    )
    (net (code "53") (name "Serail RX") (class "Default")
      (node (ref "DD1") (pin "2") (pinfunction "(RXD0/PCINT8)_PE0_2") (pintype "passive"))
      (node (ref "XP2") (pin "1") (pinfunction "1_1") (pintype "passive"))
    )
    (net (code "54") (name "Serial TX") (class "Default")
      (node (ref "DD1") (pin "3") (pinfunction "(TXD0)_PE1_3") (pintype "passive"))
      (node (ref "XP2") (pin "2") (pinfunction "2_2") (pintype "passive"))
    )
    (net (code "55") (name "VBAT") (class "Default")
      (node (ref "DD1") (pin "53") (pinfunction "PC0_(A8)_53") (pintype "passive"))
      (node (ref "R3") (pin "1") (pinfunction "1_1") (pintype "passive"))
      (node (ref "R4") (pin "2") (pinfunction "2_2") (pintype "passive"))
      (node (ref "VD19") (pin "1") (pinfunction "K_1") (pintype "passive"))
    )
    (net (code "56") (name "XTAL1") (class "Default")
      (node (ref "DD1") (pin "34") (pinfunction "XTAL1_34") (pintype "passive"))
      (node (ref "R1") (pin "2") (pinfunction "2_2") (pintype "passive"))
      (node (ref "Y1") (pin "3") (pinfunction "X1_3") (pintype "passive"))
    )
    (net (code "57") (name "XTAL2") (class "Default")
      (node (ref "DD1") (pin "33") (pinfunction "XTAL2_33") (pintype "passive"))
      (node (ref "R1") (pin "1") (pinfunction "1_1") (pintype "passive"))
      (node (ref "Y1") (pin "1") (pinfunction "X2_1") (pintype "passive"))
    )
    (net (code "58") (name "unconnected-(DD1-(CLKO{slash}ICP3{slash}INT7)_PE7-Pad9)") (class "Default")
      (node (ref "DD1") (pin "9") (pinfunction "(CLKO/ICP3/INT7)_PE7_9") (pintype "passive"))
    )
    (net (code "59") (name "unconnected-(DD1-(ICP4)_PL0-Pad35)") (class "Default")
      (node (ref "DD1") (pin "35") (pinfunction "(ICP4)_PL0_35") (pintype "passive"))
    )
    (net (code "60") (name "unconnected-(DD1-(OC0A{slash}OC1C{slash}PCINT7)_PB7-Pad26)") (class "Default")
      (node (ref "DD1") (pin "26") (pinfunction "(OC0A/OC1C/PCINT7)_PB7_26") (pintype "passive"))
    )
    (net (code "61") (name "unconnected-(DD1-(OC0B)_PG5-Pad1)") (class "Default")
      (node (ref "DD1") (pin "1") (pinfunction "(OC0B)_PG5_1") (pintype "passive"))
    )
    (net (code "62") (name "unconnected-(DD1-(OC3C{slash}INT5)_PE5-Pad7)") (class "Default")
      (node (ref "DD1") (pin "7") (pinfunction "(OC3C/INT5)_PE5_7") (pintype "passive"))
    )
    (net (code "63") (name "unconnected-(DD1-(RXD2)_PH0-Pad12)") (class "Default")
      (node (ref "DD1") (pin "12") (pinfunction "(RXD2)_PH0_12") (pintype "passive"))
    )
    (net (code "64") (name "unconnected-(DD1-(T3{slash}INT6)_PE6-Pad8)") (class "Default")
      (node (ref "DD1") (pin "8") (pinfunction "(T3/INT6)_PE6_8") (pintype "passive"))
    )
    (net (code "65") (name "unconnected-(DD1-(T4)_PH7-Pad27)") (class "Default")
      (node (ref "DD1") (pin "27") (pinfunction "(T4)_PH7_27") (pintype "passive"))
    )
    (net (code "66") (name "unconnected-(DD1-(TOSC1)_PG4-Pad29)") (class "Default")
      (node (ref "DD1") (pin "29") (pinfunction "(TOSC1)_PG4_29") (pintype "passive"))
    )
    (net (code "67") (name "unconnected-(DD1-(TOSC2)_PG3-Pad28)") (class "Default")
      (node (ref "DD1") (pin "28") (pinfunction "(TOSC2)_PG3_28") (pintype "passive"))
    )
    (net (code "68") (name "unconnected-(DD1-(XCK0{slash}AIN0)_PE2-Pad4)") (class "Default")
      (node (ref "DD1") (pin "4") (pinfunction "(XCK0/AIN0)_PE2_4") (pintype "passive"))
    )
    (net (code "69") (name "unconnected-(DD1-(~{SS}{slash}PCINT0)_PB0-Pad19)") (class "Default")
      (node (ref "DD1") (pin "19") (pinfunction "(~{SS}/PCINT0)_PB0_19") (pintype "passive"))
    )
    (net (code "70") (name "unconnected-(DD1-PA0_(AD0)-Pad78)") (class "Default")
      (node (ref "DD1") (pin "78") (pinfunction "PA0_(AD0)_78") (pintype "passive"))
    )
    (net (code "71") (name "unconnected-(DD1-PA1_(AD1)-Pad77)") (class "Default")
      (node (ref "DD1") (pin "77") (pinfunction "PA1_(AD1)_77") (pintype "passive"))
    )
    (net (code "72") (name "unconnected-(DD1-PA2_(AD2)-Pad76)") (class "Default")
      (node (ref "DD1") (pin "76") (pinfunction "PA2_(AD2)_76") (pintype "passive"))
    )
    (net (code "73") (name "unconnected-(DD1-PA3_(AD3)-Pad75)") (class "Default")
      (node (ref "DD1") (pin "75") (pinfunction "PA3_(AD3)_75") (pintype "passive"))
    )
    (net (code "74") (name "unconnected-(DD1-PA4_(AD4)-Pad74)") (class "Default")
      (node (ref "DD1") (pin "74") (pinfunction "PA4_(AD4)_74") (pintype "passive"))
    )
    (net (code "75") (name "unconnected-(DD1-PA5_(AD5)-Pad73)") (class "Default")
      (node (ref "DD1") (pin "73") (pinfunction "PA5_(AD5)_73") (pintype "passive"))
    )
    (net (code "76") (name "unconnected-(DD1-PA6_(AD6)-Pad72)") (class "Default")
      (node (ref "DD1") (pin "72") (pinfunction "PA6_(AD6)_72") (pintype "passive"))
    )
    (net (code "77") (name "unconnected-(DD1-PA7_(AD7)-Pad71)") (class "Default")
      (node (ref "DD1") (pin "71") (pinfunction "PA7_(AD7)_71") (pintype "passive"))
    )
    (net (code "78") (name "unconnected-(DD1-PC1_(A9)-Pad54)") (class "Default")
      (node (ref "DD1") (pin "54") (pinfunction "PC1_(A9)_54") (pintype "passive"))
    )
    (net (code "79") (name "unconnected-(DD1-PC2_(A10)-Pad55)") (class "Default")
      (node (ref "DD1") (pin "55") (pinfunction "PC2_(A10)_55") (pintype "passive"))
    )
    (net (code "80") (name "unconnected-(DD1-PC3_(A11)-Pad56)") (class "Default")
      (node (ref "DD1") (pin "56") (pinfunction "PC3_(A11)_56") (pintype "passive"))
    )
    (net (code "81") (name "unconnected-(DD1-PC4_(A12)-Pad57)") (class "Default")
      (node (ref "DD1") (pin "57") (pinfunction "PC4_(A12)_57") (pintype "passive"))
    )
    (net (code "82") (name "unconnected-(DD1-PC5_(A13)-Pad58)") (class "Default")
      (node (ref "DD1") (pin "58") (pinfunction "PC5_(A13)_58") (pintype "passive"))
    )
    (net (code "83") (name "unconnected-(DD1-PC6_(A14)-Pad59)") (class "Default")
      (node (ref "DD1") (pin "59") (pinfunction "PC6_(A14)_59") (pintype "passive"))
    )
    (net (code "84") (name "unconnected-(DD1-PC7_(A15)-Pad60)") (class "Default")
      (node (ref "DD1") (pin "60") (pinfunction "PC7_(A15)_60") (pintype "passive"))
    )
    (net (code "85") (name "unconnected-(DD1-PF0_(ADC0)-Pad97)") (class "Default")
      (node (ref "DD1") (pin "97") (pinfunction "PF0_(ADC0)_97") (pintype "passive"))
    )
    (net (code "86") (name "unconnected-(DD1-PF1_(ADC1)-Pad96)") (class "Default")
      (node (ref "DD1") (pin "96") (pinfunction "PF1_(ADC1)_96") (pintype "passive"))
    )
    (net (code "87") (name "unconnected-(DD1-PF2_(ADC2)-Pad95)") (class "Default")
      (node (ref "DD1") (pin "95") (pinfunction "PF2_(ADC2)_95") (pintype "passive"))
    )
    (net (code "88") (name "unconnected-(DD1-PF3_(ADC3)-Pad94)") (class "Default")
      (node (ref "DD1") (pin "94") (pinfunction "PF3_(ADC3)_94") (pintype "passive"))
    )
    (net (code "89") (name "unconnected-(DD1-PF4_(ADC4{slash}TCK)-Pad93)") (class "Default")
      (node (ref "DD1") (pin "93") (pinfunction "PF4_(ADC4/TCK)_93") (pintype "passive"))
    )
    (net (code "90") (name "unconnected-(DD1-PF5_(ADC5{slash}TMS)-Pad92)") (class "Default")
      (node (ref "DD1") (pin "92") (pinfunction "PF5_(ADC5/TMS)_92") (pintype "passive"))
    )
    (net (code "91") (name "unconnected-(DD1-PF6_(ADC6{slash}TDO)-Pad91)") (class "Default")
      (node (ref "DD1") (pin "91") (pinfunction "PF6_(ADC6/TDO)_91") (pintype "passive"))
    )
    (net (code "92") (name "unconnected-(DD1-PF7_(ADC7{slash}TDI)-Pad90)") (class "Default")
      (node (ref "DD1") (pin "90") (pinfunction "PF7_(ADC7/TDI)_90") (pintype "passive"))
    )
    (net (code "93") (name "unconnected-(DD1-PG0_(~{WR)}-Pad51)") (class "Default")
      (node (ref "DD1") (pin "51") (pinfunction "PG0_(~{WR)}_51") (pintype "passive"))
    )
    (net (code "94") (name "unconnected-(DD1-PG1_(~{RD)}-Pad52)") (class "Default")
      (node (ref "DD1") (pin "52") (pinfunction "PG1_(~{RD)}_52") (pintype "passive"))
    )
    (net (code "95") (name "unconnected-(DD1-PG2_(ALE)-Pad70)") (class "Default")
      (node (ref "DD1") (pin "70") (pinfunction "PG2_(ALE)_70") (pintype "passive"))
    )
    (net (code "96") (name "unconnected-(DD1-PJ0_(RXD3{slash}PCINT9)-Pad63)") (class "Default")
      (node (ref "DD1") (pin "63") (pinfunction "PJ0_(RXD3/PCINT9)_63") (pintype "passive"))
    )
    (net (code "97") (name "unconnected-(DD1-PJ1_(TXD3{slash}PCINT10)-Pad64)") (class "Default")
      (node (ref "DD1") (pin "64") (pinfunction "PJ1_(TXD3/PCINT10)_64") (pintype "passive"))
    )
    (net (code "98") (name "unconnected-(DD1-PJ2_(XCK3{slash}PCINT11)-Pad65)") (class "Default")
      (node (ref "DD1") (pin "65") (pinfunction "PJ2_(XCK3/PCINT11)_65") (pintype "passive"))
    )
    (net (code "99") (name "unconnected-(DD1-PJ3_(PCINT12)-Pad66)") (class "Default")
      (node (ref "DD1") (pin "66") (pinfunction "PJ3_(PCINT12)_66") (pintype "passive"))
    )
    (net (code "100") (name "unconnected-(DD1-PJ4_(PCINT13)-Pad67)") (class "Default")
      (node (ref "DD1") (pin "67") (pinfunction "PJ4_(PCINT13)_67") (pintype "passive"))
    )
    (net (code "101") (name "unconnected-(DD1-PJ5_(PCINT14)-Pad68)") (class "Default")
      (node (ref "DD1") (pin "68") (pinfunction "PJ5_(PCINT14)_68") (pintype "passive"))
    )
    (net (code "102") (name "unconnected-(DD1-PJ6_(PCINT15)-Pad69)") (class "Default")
      (node (ref "DD1") (pin "69") (pinfunction "PJ6_(PCINT15)_69") (pintype "passive"))
    )
    (net (code "103") (name "unconnected-(DD1-PJ7-Pad79)") (class "Default")
      (node (ref "DD1") (pin "79") (pinfunction "PJ7_79") (pintype "passive"))
    )
    (net (code "104") (name "unconnected-(DD1-PK0_(ADC8{slash}PCINT16)-Pad89)") (class "Default")
      (node (ref "DD1") (pin "89") (pinfunction "PK0_(ADC8/PCINT16)_89") (pintype "passive"))
    )
    (net (code "105") (name "unconnected-(DD1-PK1_(ADC9{slash}PCINT17)-Pad88)") (class "Default")
      (node (ref "DD1") (pin "88") (pinfunction "PK1_(ADC9/PCINT17)_88") (pintype "passive"))
    )
    (net (code "106") (name "unconnected-(DD1-PK2_(ADC10{slash}PCINT18)-Pad87)") (class "Default")
      (node (ref "DD1") (pin "87") (pinfunction "PK2_(ADC10/PCINT18)_87") (pintype "passive"))
    )
    (net (code "107") (name "unconnected-(DD1-PK3_(ADC11{slash}PCINT19)-Pad86)") (class "Default")
      (node (ref "DD1") (pin "86") (pinfunction "PK3_(ADC11/PCINT19)_86") (pintype "passive"))
    )
    (net (code "108") (name "unconnected-(DD1-PK4_(ADC12{slash}PCINT20)-Pad85)") (class "Default")
      (node (ref "DD1") (pin "85") (pinfunction "PK4_(ADC12/PCINT20)_85") (pintype "passive"))
    )
    (net (code "109") (name "unconnected-(DD1-PK5_(ADC13{slash}PCINT21)-Pad84)") (class "Default")
      (node (ref "DD1") (pin "84") (pinfunction "PK5_(ADC13/PCINT21)_84") (pintype "passive"))
    )
    (net (code "110") (name "unconnected-(DD1-PK6_(ADC14{slash}PCINT22)-Pad83)") (class "Default")
      (node (ref "DD1") (pin "83") (pinfunction "PK6_(ADC14/PCINT22)_83") (pintype "passive"))
    )
    (net (code "111") (name "unconnected-(DD1-PK7_(ADC15{slash}PCINT23)-Pad82)") (class "Default")
      (node (ref "DD1") (pin "82") (pinfunction "PK7_(ADC15/PCINT23)_82") (pintype "passive"))
    )
    (net (code "112") (name "unconnected-(VD19-A-Pad2)") (class "Default")
      (node (ref "VD19") (pin "2") (pinfunction "A_2") (pintype "passive"))
    )
    (net (code "113") (name "unconnected-(XS1-Pad8)") (class "Default")
      (node (ref "XS1") (pin "8") (pinfunction "8_8") (pintype "passive"))
    )
    (net (code "114") (name "unconnected-(XS2-Pad5)") (class "Default")
      (node (ref "XS2") (pin "5") (pinfunction "5_5") (pintype "passive"))
    )
    (net (code "115") (name "unconnected-(XS2-Pad6)") (class "Default")
      (node (ref "XS2") (pin "6") (pinfunction "6_6") (pintype "passive"))
    )
    (net (code "116") (name "unconnected-(XS4-Pad2)") (class "Default")
      (node (ref "XS4") (pin "2") (pinfunction "2_2") (pintype "passive"))
    )
  )
)
